# rf_trsw.net
KiCad netlist of a schematic drawn in Altium Designer
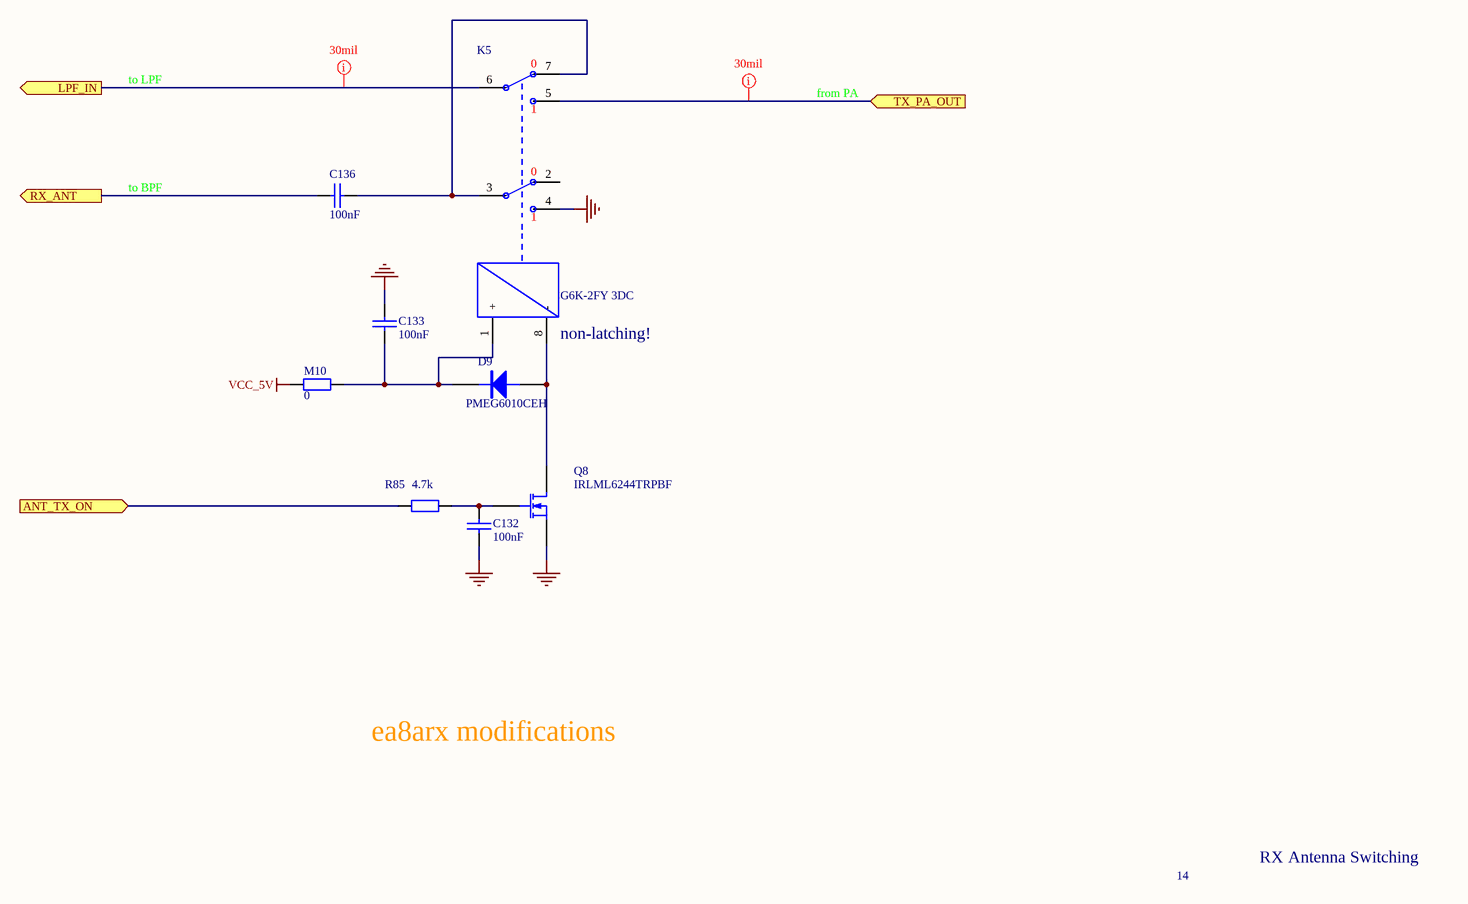
[diagram p0: rf_trsw.SchDoc]

(export (version "E")
  (design (tool "Eeschema 10.0.6"))
  (components
    (comp (ref "C132")
      (value "100nF")
      (footprint "0805")
      (description "Capacitor")
      (fields (field (name "VOLTAGE") "100V"))
      (libsource (lib "mcHF_rf") (part "CAP"))
    )
    (comp (ref "C133")
      (value "100nF")
      (footprint "0805")
      (description "Capacitor")
      (fields (field (name "VOLTAGE") "100V"))
      (libsource (lib "mcHF_rf") (part "CAP"))
    )
    (comp (ref "C136")
      (value "100nF")
      (footprint "0805")
      (description "Capacitor")
      (fields (field (name "VOLTAGE") "100V"))
      (libsource (lib "mcHF_rf") (part "CAP"))
    )
    (comp (ref "D9")
      (value "PMEG6010CEH")
      (footprint "SOD87")
      (description "DIODE, SCHOTTKY, 1A, 60V, SOD-123F")
      (libsource (lib "mcHF_rf") (part "PMEG6010CEH"))
    )
    (comp (ref "K5")
      (value "G6K-2FY 3DC")
      (footprint "Omron_2FY")
      (description "Single-winding Latching Relay")
      (libsource (lib "mcHF_rf") (part "G6KU-2FY 3DC"))
    )
    (comp (ref "M10")
      (value "0")
      (footprint "0805")
      (description "Resistor")
      (libsource (lib "mcHF_rf") (part "RES"))
    )
    (comp (ref "Q8")
      (value "IRLML6244TRPBF")
      (footprint "SOT-23-Pro")
      (description "N-Channel MOSFET")
      (libsource (lib "mcHF_ui_b") (part "MOSFET-N"))
    )
    (comp (ref "R85")
      (value "4.7k")
      (footprint "0805")
      (description "Resistor")
      (libsource (lib "") (part "RES_1"))
    )
  )
  (nets
    (net (code "1") (name "/ANT_TX_ON") (class "Default")
      (node (ref "R85") (pin "1") (pinfunction "1_1") (pintype "passive"))
    )
    (net (code "2") (name "/LPF_IN") (class "Default")
      (node (ref "K5") (pin "6") (pinfunction "6_6") (pintype "passive"))
    )
    (net (code "3") (name "/RX_ANT") (class "Default")
      (node (ref "C136") (pin "1") (pinfunction "1_1") (pintype "passive"))
    )
    (net (code "4") (name "/TX_PA_OUT") (class "Default")
      (node (ref "K5") (pin "5") (pinfunction "5_5") (pintype "passive"))
    )
    (net (code "5") (name "GND") (class "Default")
      (node (ref "C132") (pin "1") (pinfunction "1_1") (pintype "passive"))
      (node (ref "C133") (pin "2") (pinfunction "2_2") (pintype "passive"))
      (node (ref "K5") (pin "4") (pinfunction "4_4") (pintype "passive"))
      (node (ref "Q8") (pin "2") (pinfunction "S_2") (pintype "passive"))
    )
    (net (code "6") (name "Net-(C136-Pad2)") (class "Default")
      (node (ref "C136") (pin "2") (pinfunction "2_2") (pintype "passive"))
      (node (ref "K5") (pin "3") (pinfunction "3_3") (pintype "passive"))
      (node (ref "K5") (pin "7") (pinfunction "7_7") (pintype "passive"))
    )
    (net (code "7") (name "Net-(D9-A)") (class "Default")
      (node (ref "D9") (pin "1") (pinfunction "A_1") (pintype "passive"))
      (node (ref "K5") (pin "8") (pinfunction "-_8") (pintype "passive"))
      (node (ref "Q8") (pin "3") (pinfunction "D_3") (pintype "passive"))
    )
    (net (code "8") (name "Net-(D9-K)") (class "Default")
      (node (ref "C133") (pin "1") (pinfunction "1_1") (pintype "passive"))
      (node (ref "D9") (pin "2") (pinfunction "K_2") (pintype "passive"))
      (node (ref "K5") (pin "1") (pinfunction "+_1") (pintype "passive"))
      (node (ref "M10") (pin "1") (pinfunction "1_1") (pintype "passive"))
    )
    (net (code "9") (name "Net-(Q8-G)") (class "Default")
      (node (ref "C132") (pin "2") (pinfunction "2_2") (pintype "passive"))
      (node (ref "Q8") (pin "1") (pinfunction "G_1") (pintype "passive"))
      (node (ref "R85") (pin "2") (pinfunction "2_2") (pintype "passive"))
    )
    (net (code "10") (name "VCC_5V") (class "Default")
      (node (ref "M10") (pin "2") (pinfunction "2_2") (pintype "passive"))
    )
    (net (code "11") (name "unconnected-(K5-Pad2)") (class "Default")
      (node (ref "K5") (pin "2") (pinfunction "2_2") (pintype "passive"))
    )
  )
)
